# xcore_A.net
KiCad netlist of a schematic drawn in EAGLE
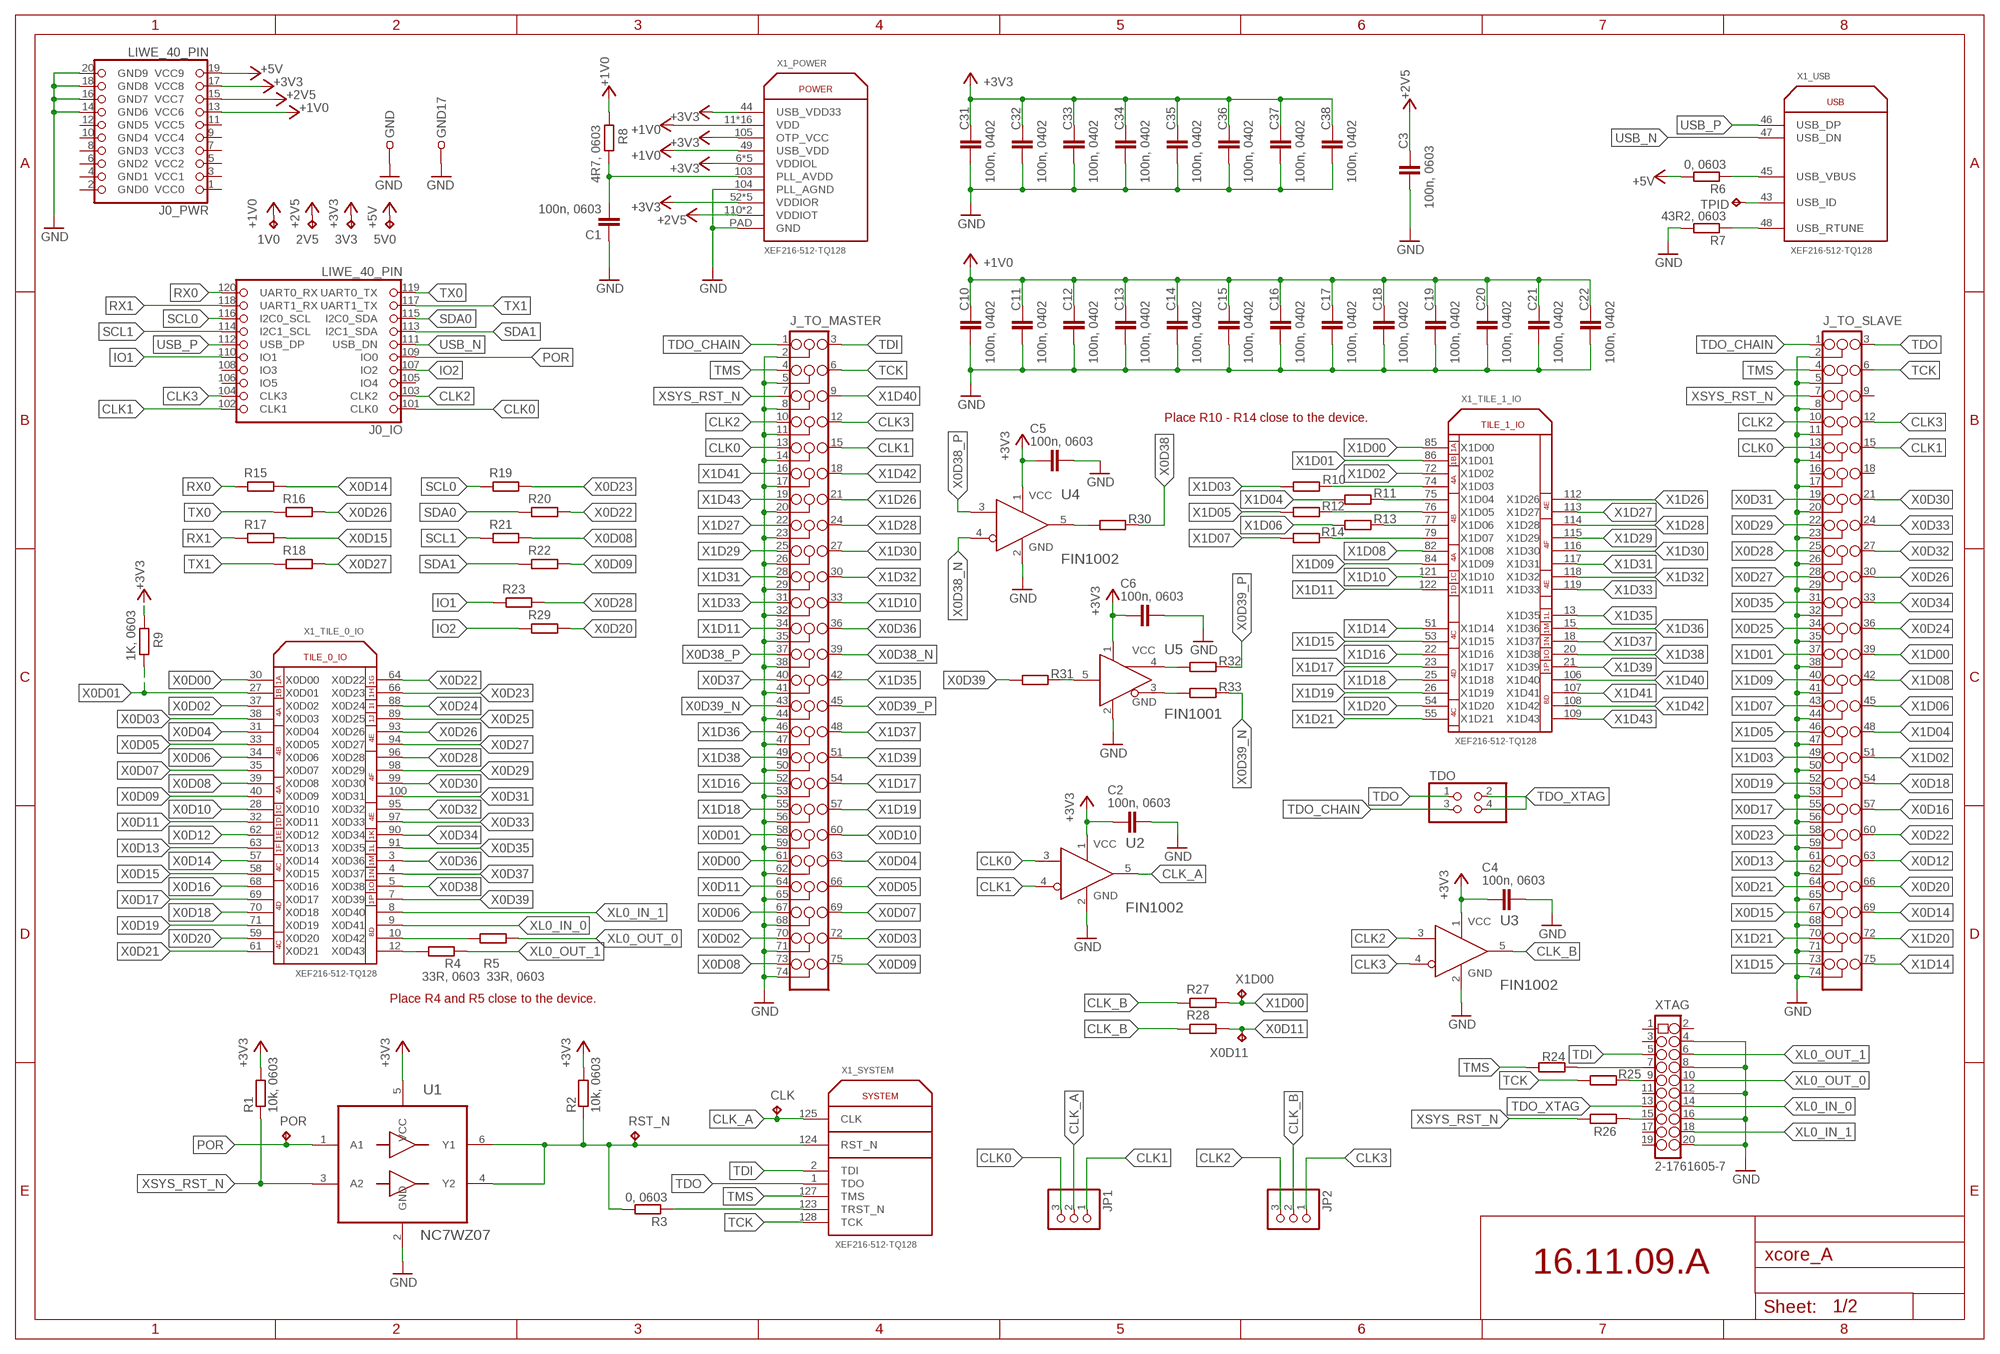
[diagram p0: schematic, sheet 1]
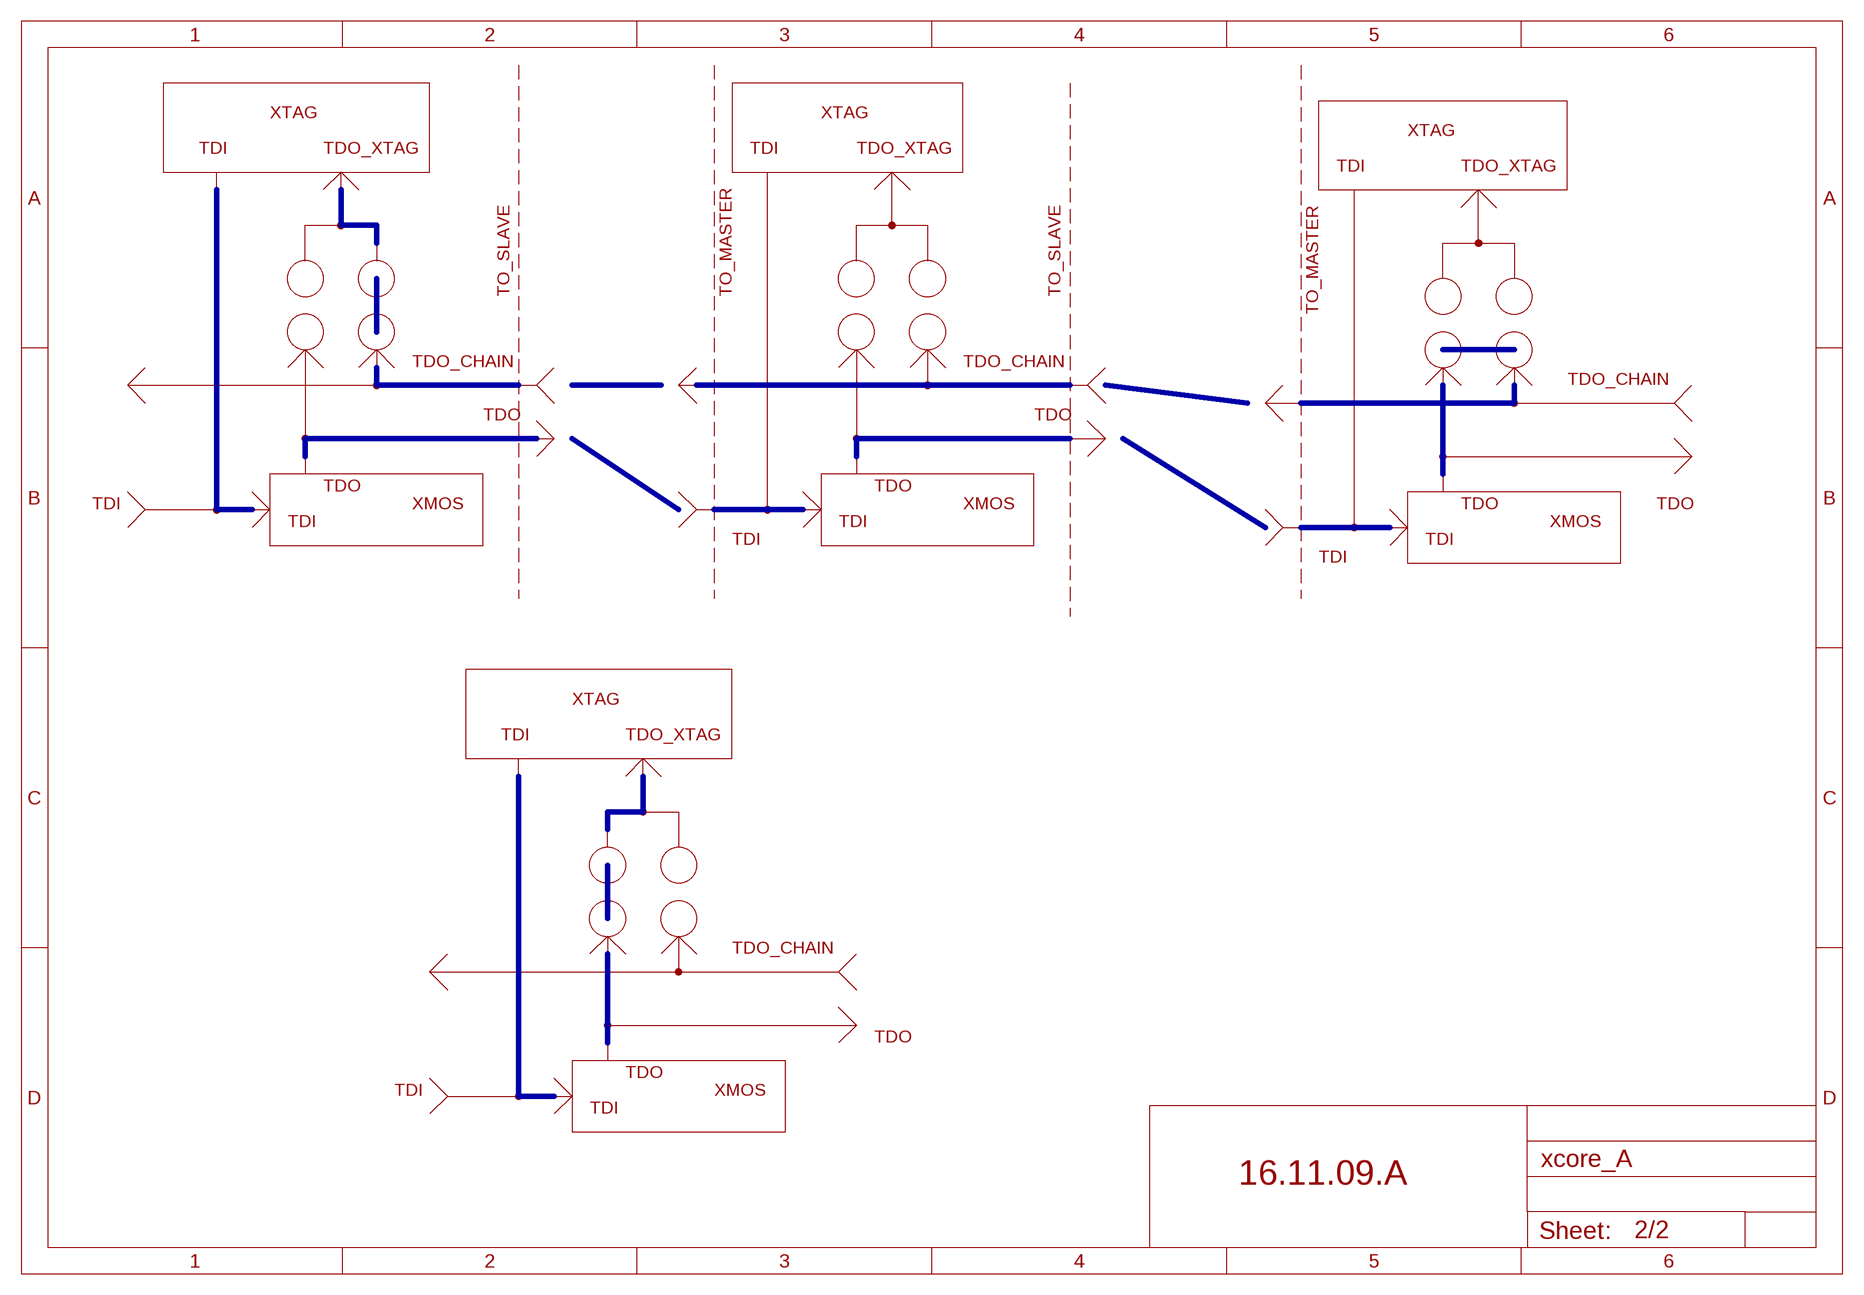
[diagram p1: schematic, sheet 2]

(export (version "E")
  (design (tool "Eeschema 10.0.6"))
  (components
    (comp (ref "1V0")
      (value "TPTP14R")
      (footprint "eagle-import:TP14R")
      (libsource (lib "eagle-import") (part "TPTP14R"))
    )
    (comp (ref "2V5")
      (value "TPTP14R")
      (footprint "eagle-import:TP14R")
      (libsource (lib "eagle-import") (part "TPTP14R"))
    )
    (comp (ref "3V3")
      (value "TPTP14R")
      (footprint "eagle-import:TP14R")
      (libsource (lib "eagle-import") (part "TPTP14R"))
    )
    (comp (ref "5V0")
      (value "TPTP14R")
      (footprint "eagle-import:TP14R")
      (libsource (lib "eagle-import") (part "TPTP14R"))
    )
    (comp (ref "C1")
      (value "100n, 0603")
      (footprint "eagle-import:C0603")
      (libsource (lib "eagle-import") (part "C-EUC0603"))
    )
    (comp (ref "C2")
      (value "100n, 0603")
      (footprint "eagle-import:C0603")
      (libsource (lib "eagle-import") (part "C-EUC0603"))
    )
    (comp (ref "C3")
      (value "100n, 0603")
      (footprint "eagle-import:C0402K")
      (libsource (lib "eagle-import") (part "C-EUC0402K"))
    )
    (comp (ref "C4")
      (value "100n, 0603")
      (footprint "eagle-import:C0603")
      (libsource (lib "eagle-import") (part "C-EUC0603"))
    )
    (comp (ref "C5")
      (value "100n, 0603")
      (footprint "eagle-import:C0603")
      (libsource (lib "eagle-import") (part "C-EUC0603"))
    )
    (comp (ref "C6")
      (value "100n, 0603")
      (footprint "eagle-import:C0603")
      (libsource (lib "eagle-import") (part "C-EUC0603"))
    )
    (comp (ref "C10")
      (value "100n, 0402")
      (footprint "eagle-import:C0402K")
      (libsource (lib "eagle-import") (part "C-EUC0402K"))
    )
    (comp (ref "C11")
      (value "100n, 0402")
      (footprint "eagle-import:C0402K")
      (libsource (lib "eagle-import") (part "C-EUC0402K"))
    )
    (comp (ref "C12")
      (value "100n, 0402")
      (footprint "eagle-import:C0402K")
      (libsource (lib "eagle-import") (part "C-EUC0402K"))
    )
    (comp (ref "C13")
      (value "100n, 0402")
      (footprint "eagle-import:C0402K")
      (libsource (lib "eagle-import") (part "C-EUC0402K"))
    )
    (comp (ref "C14")
      (value "100n, 0402")
      (footprint "eagle-import:C0402K")
      (libsource (lib "eagle-import") (part "C-EUC0402K"))
    )
    (comp (ref "C15")
      (value "100n, 0402")
      (footprint "eagle-import:C0402K")
      (libsource (lib "eagle-import") (part "C-EUC0402K"))
    )
    (comp (ref "C16")
      (value "100n, 0402")
      (footprint "eagle-import:C0402K")
      (libsource (lib "eagle-import") (part "C-EUC0402K"))
    )
    (comp (ref "C17")
      (value "100n, 0402")
      (footprint "eagle-import:C0402K")
      (libsource (lib "eagle-import") (part "C-EUC0402K"))
    )
    (comp (ref "C18")
      (value "100n, 0402")
      (footprint "eagle-import:C0402K")
      (libsource (lib "eagle-import") (part "C-EUC0402K"))
    )
    (comp (ref "C19")
      (value "100n, 0402")
      (footprint "eagle-import:C0402K")
      (libsource (lib "eagle-import") (part "C-EUC0402K"))
    )
    (comp (ref "C20")
      (value "100n, 0402")
      (footprint "eagle-import:C0402K")
      (libsource (lib "eagle-import") (part "C-EUC0402K"))
    )
    (comp (ref "C21")
      (value "100n, 0402")
      (footprint "eagle-import:C0402K")
      (libsource (lib "eagle-import") (part "C-EUC0402K"))
    )
    (comp (ref "C22")
      (value "100n, 0402")
      (footprint "eagle-import:C0402K")
      (libsource (lib "eagle-import") (part "C-EUC0402K"))
    )
    (comp (ref "C31")
      (value "100n, 0402")
      (footprint "eagle-import:C0402K")
      (libsource (lib "eagle-import") (part "C-EUC0402K"))
    )
    (comp (ref "C32")
      (value "100n, 0402")
      (footprint "eagle-import:C0402K")
      (libsource (lib "eagle-import") (part "C-EUC0402K"))
    )
    (comp (ref "C33")
      (value "100n, 0402")
      (footprint "eagle-import:C0402K")
      (libsource (lib "eagle-import") (part "C-EUC0402K"))
    )
    (comp (ref "C34")
      (value "100n, 0402")
      (footprint "eagle-import:C0402K")
      (libsource (lib "eagle-import") (part "C-EUC0402K"))
    )
    (comp (ref "C35")
      (value "100n, 0402")
      (footprint "eagle-import:C0402K")
      (libsource (lib "eagle-import") (part "C-EUC0402K"))
    )
    (comp (ref "C36")
      (value "100n, 0402")
      (footprint "eagle-import:C0402K")
      (libsource (lib "eagle-import") (part "C-EUC0402K"))
    )
    (comp (ref "C37")
      (value "100n, 0402")
      (footprint "eagle-import:C0402K")
      (libsource (lib "eagle-import") (part "C-EUC0402K"))
    )
    (comp (ref "C38")
      (value "100n, 0402")
      (footprint "eagle-import:C0402K")
      (libsource (lib "eagle-import") (part "C-EUC0402K"))
    )
    (comp (ref "CLK")
      (value "TPTP14R")
      (footprint "eagle-import:TP14R")
      (libsource (lib "eagle-import") (part "TPTP14R"))
    )
    (comp (ref "GND")
      (value "TEST-22-MULTICOMP")
      (footprint "eagle-import:TEST_1MM")
      (libsource (lib "eagle-import") (part "TEST-22-MULTICOMP"))
    )
    (comp (ref "GND17")
      (value "TEST-22-MULTICOMP")
      (footprint "eagle-import:TEST_1MM")
      (libsource (lib "eagle-import") (part "TEST-22-MULTICOMP"))
    )
    (comp (ref "J0")
      (value "LIWE_40_PIN")
      (footprint "eagle-import:LIWE_40_PIN_8X8")
      (libsource (lib "eagle-import") (part "LIWE_40_PIN"))
    )
    (comp (ref "JP1")
      (value "PINHD-1X3")
      (footprint "eagle-import:1X03")
      (libsource (lib "eagle-import") (part "PINHD-1X3"))
    )
    (comp (ref "JP2")
      (value "PINHD-1X3")
      (footprint "eagle-import:1X03")
      (libsource (lib "eagle-import") (part "PINHD-1X3"))
    )
    (comp (ref "J_TO_MASTER")
      (value "TSW-125-08-G-T-RA")
      (footprint "eagle-import:3X25_90_M")
      (libsource (lib "eagle-import") (part "PINHD-3X25/90/M"))
    )
    (comp (ref "J_TO_SLAVE")
      (value "TSW-125-08-G-T-RA")
      (footprint "eagle-import:3X25_90")
      (libsource (lib "eagle-import") (part "PINHD-3X25/90"))
    )
    (comp (ref "POR")
      (value "TPTP14R")
      (footprint "eagle-import:TP14R")
      (libsource (lib "eagle-import") (part "TPTP14R"))
    )
    (comp (ref "R1")
      (value "10k, 0603")
      (footprint "eagle-import:R0603")
      (libsource (lib "eagle-import") (part "R-EU_R0603"))
    )
    (comp (ref "R2")
      (value "10k, 0603")
      (footprint "eagle-import:R0603")
      (libsource (lib "eagle-import") (part "R-EU_R0603"))
    )
    (comp (ref "R3")
      (value "0, 0603")
      (footprint "eagle-import:R0603")
      (libsource (lib "eagle-import") (part "R-EU_R0603"))
    )
    (comp (ref "R4")
      (value "33R, 0603")
      (footprint "eagle-import:R0603")
      (libsource (lib "eagle-import") (part "R-EU_R0603"))
    )
    (comp (ref "R5")
      (value "33R, 0603")
      (footprint "eagle-import:R0603")
      (libsource (lib "eagle-import") (part "R-EU_R0603"))
    )
    (comp (ref "R6")
      (value "0, 0603")
      (footprint "eagle-import:R0603")
      (libsource (lib "eagle-import") (part "R-EU_R0603"))
    )
    (comp (ref "R7")
      (value "43R2, 0603")
      (footprint "eagle-import:R0603")
      (libsource (lib "eagle-import") (part "R-EU_R0603"))
    )
    (comp (ref "R8")
      (value "4R7, 0603")
      (footprint "eagle-import:R0603")
      (libsource (lib "eagle-import") (part "R-EU_R0603"))
    )
    (comp (ref "R9")
      (value "1K, 0603")
      (footprint "eagle-import:R0603")
      (libsource (lib "eagle-import") (part "R-EU_R0603"))
    )
    (comp (ref "R10")
      (value "R-EU_R0603")
      (footprint "eagle-import:R0603")
      (libsource (lib "eagle-import") (part "R-EU_R0603"))
    )
    (comp (ref "R11")
      (value "R-EU_R0603")
      (footprint "eagle-import:R0603")
      (libsource (lib "eagle-import") (part "R-EU_R0603"))
    )
    (comp (ref "R12")
      (value "R-EU_R0603")
      (footprint "eagle-import:R0603")
      (libsource (lib "eagle-import") (part "R-EU_R0603"))
    )
    (comp (ref "R13")
      (value "R-EU_R0603")
      (footprint "eagle-import:R0603")
      (libsource (lib "eagle-import") (part "R-EU_R0603"))
    )
    (comp (ref "R14")
      (value "R-EU_R0603")
      (footprint "eagle-import:R0603")
      (libsource (lib "eagle-import") (part "R-EU_R0603"))
    )
    (comp (ref "R15")
      (value "R-EU_R0603")
      (footprint "eagle-import:R0603")
      (libsource (lib "eagle-import") (part "R-EU_R0603"))
    )
    (comp (ref "R16")
      (value "R-EU_R0603")
      (footprint "eagle-import:R0603")
      (libsource (lib "eagle-import") (part "R-EU_R0603"))
    )
    (comp (ref "R17")
      (value "R-EU_R0603")
      (footprint "eagle-import:R0603")
      (libsource (lib "eagle-import") (part "R-EU_R0603"))
    )
    (comp (ref "R18")
      (value "R-EU_R0603")
      (footprint "eagle-import:R0603")
      (libsource (lib "eagle-import") (part "R-EU_R0603"))
    )
    (comp (ref "R19")
      (value "R-EU_R0603")
      (footprint "eagle-import:R0603")
      (libsource (lib "eagle-import") (part "R-EU_R0603"))
    )
    (comp (ref "R20")
      (value "R-EU_R0603")
      (footprint "eagle-import:R0603")
      (libsource (lib "eagle-import") (part "R-EU_R0603"))
    )
    (comp (ref "R21")
      (value "R-EU_R0603")
      (footprint "eagle-import:R0603")
      (libsource (lib "eagle-import") (part "R-EU_R0603"))
    )
    (comp (ref "R22")
      (value "R-EU_R0603")
      (footprint "eagle-import:R0603")
      (libsource (lib "eagle-import") (part "R-EU_R0603"))
    )
    (comp (ref "R23")
      (value "R-EU_R0603")
      (footprint "eagle-import:R0603")
      (libsource (lib "eagle-import") (part "R-EU_R0603"))
    )
    (comp (ref "R24")
      (value "R-EU_R0603")
      (footprint "eagle-import:R0603")
      (libsource (lib "eagle-import") (part "R-EU_R0603"))
    )
    (comp (ref "R25")
      (value "R-EU_R0603")
      (footprint "eagle-import:R0603")
      (libsource (lib "eagle-import") (part "R-EU_R0603"))
    )
    (comp (ref "R26")
      (value "R-EU_R0603")
      (footprint "eagle-import:R0603")
      (libsource (lib "eagle-import") (part "R-EU_R0603"))
    )
    (comp (ref "R27")
      (value "R-EU_R0603")
      (footprint "eagle-import:R0603")
      (libsource (lib "eagle-import") (part "R-EU_R0603"))
    )
    (comp (ref "R28")
      (value "R-EU_R0603")
      (footprint "eagle-import:R0603")
      (libsource (lib "eagle-import") (part "R-EU_R0603"))
    )
    (comp (ref "R29")
      (value "R-EU_R0603")
      (footprint "eagle-import:R0603")
      (libsource (lib "eagle-import") (part "R-EU_R0603"))
    )
    (comp (ref "R30")
      (value "R-EU_R0603")
      (footprint "eagle-import:R0603")
      (libsource (lib "eagle-import") (part "R-EU_R0603"))
    )
    (comp (ref "R31")
      (value "R-EU_R0603")
      (footprint "eagle-import:R0603")
      (libsource (lib "eagle-import") (part "R-EU_R0603"))
    )
    (comp (ref "R32")
      (value "R-EU_R0603")
      (footprint "eagle-import:R0603")
      (libsource (lib "eagle-import") (part "R-EU_R0603"))
    )
    (comp (ref "R33")
      (value "R-EU_R0603")
      (footprint "eagle-import:R0603")
      (libsource (lib "eagle-import") (part "R-EU_R0603"))
    )
    (comp (ref "RST_N")
      (value "TPTP14R")
      (footprint "eagle-import:TP14R")
      (libsource (lib "eagle-import") (part "TPTP14R"))
    )
    (comp (ref "TDO")
      (value "PINHD-2X2")
      (footprint "eagle-import:2X02")
      (libsource (lib "eagle-import") (part "PINHD-2X2"))
    )
    (comp (ref "TPID")
      (value "TPB1,27")
      (footprint "eagle-import:B1,27")
      (libsource (lib "eagle-import") (part "TPB1,27"))
    )
    (comp (ref "U1")
      (value "NC7WZ07")
      (footprint "eagle-import:SOT65P210X110-6N")
      (libsource (lib "eagle-import") (part "NC7WZ07"))
    )
    (comp (ref "U2")
      (value "FIN1002")
      (footprint "eagle-import:SOT95P280X140-5N")
      (libsource (lib "eagle-import") (part "FIN1002"))
    )
    (comp (ref "U3")
      (value "FIN1002")
      (footprint "eagle-import:SOT95P280X140-5N")
      (libsource (lib "eagle-import") (part "FIN1002"))
    )
    (comp (ref "U4")
      (value "FIN1002")
      (footprint "eagle-import:SOT95P280X140-5N")
      (libsource (lib "eagle-import") (part "FIN1002"))
    )
    (comp (ref "U5")
      (value "FIN1001")
      (footprint "eagle-import:SOT95P280X140-5N")
      (libsource (lib "eagle-import") (part "FIN1001"))
    )
    (comp (ref "X0D11")
      (value "TPTP14R")
      (footprint "eagle-import:TP14R")
      (libsource (lib "eagle-import") (part "TPTP14R"))
    )
    (comp (ref "X1")
      (value "XEF216-512-TQ128")
      (footprint "eagle-import:TQFP128")
      (libsource (lib "eagle-import") (part "XEF216-512-TQ128"))
    )
    (comp (ref "X1D00")
      (value "TPTP14R")
      (footprint "eagle-import:TP14R")
      (libsource (lib "eagle-import") (part "TPTP14R"))
    )
    (comp (ref "XTAG")
      (value "2-1761605-7")
      (footprint "eagle-import:2X10")
      (libsource (lib "eagle-import") (part "PINHD-2X10"))
    )
  )
  (nets
    (net (code "1") (name "+1V0") (class "Default")
      (node (ref "1V0") (pin "TP") (pinfunction "TP_TP") (pintype "input"))
      (node (ref "C10") (pin "2") (pinfunction "2_2") (pintype "passive"))
      (node (ref "C11") (pin "2") (pinfunction "2_2") (pintype "passive"))
      (node (ref "C12") (pin "2") (pinfunction "2_2") (pintype "passive"))
      (node (ref "C13") (pin "2") (pinfunction "2_2") (pintype "passive"))
      (node (ref "C14") (pin "2") (pinfunction "2_2") (pintype "passive"))
      (node (ref "C15") (pin "2") (pinfunction "2_2") (pintype "passive"))
      (node (ref "C16") (pin "2") (pinfunction "2_2") (pintype "passive"))
      (node (ref "C17") (pin "2") (pinfunction "2_2") (pintype "passive"))
      (node (ref "C18") (pin "2") (pinfunction "2_2") (pintype "passive"))
      (node (ref "C19") (pin "2") (pinfunction "2_2") (pintype "passive"))
      (node (ref "C20") (pin "2") (pinfunction "2_2") (pintype "passive"))
      (node (ref "C21") (pin "2") (pinfunction "2_2") (pintype "passive"))
      (node (ref "C22") (pin "2") (pinfunction "2_2") (pintype "passive"))
      (node (ref "J0") (pin "13") (pinfunction "VCC6_13") (pintype "passive"))
      (node (ref "R8") (pin "1") (pinfunction "1_1") (pintype "passive"))
      (node (ref "X1") (pin "101") (pinfunction "VDD_101") (pintype "bidirectional"))
      (node (ref "X1") (pin "102") (pinfunction "VDD_102") (pintype "bidirectional"))
      (node (ref "X1") (pin "11") (pinfunction "VDD_11") (pintype "bidirectional"))
      (node (ref "X1") (pin "120") (pinfunction "VDD_120") (pintype "bidirectional"))
      (node (ref "X1") (pin "126") (pinfunction "VDD_126") (pintype "bidirectional"))
      (node (ref "X1") (pin "16") (pinfunction "VDD_16") (pintype "bidirectional"))
      (node (ref "X1") (pin "17") (pinfunction "VDD_17") (pintype "bidirectional"))
      (node (ref "X1") (pin "24") (pinfunction "VDD_24") (pintype "bidirectional"))
      (node (ref "X1") (pin "36") (pinfunction "VDD_36") (pintype "bidirectional"))
      (node (ref "X1") (pin "41") (pinfunction "VDD_41") (pintype "bidirectional"))
      (node (ref "X1") (pin "49") (pinfunction "USB_VDD_49") (pintype "bidirectional"))
      (node (ref "X1") (pin "56") (pinfunction "VDD_56") (pintype "bidirectional"))
      (node (ref "X1") (pin "60") (pinfunction "VDD_60") (pintype "bidirectional"))
      (node (ref "X1") (pin "73") (pinfunction "VDD_73") (pintype "bidirectional"))
      (node (ref "X1") (pin "80") (pinfunction "VDD_80") (pintype "bidirectional"))
      (node (ref "X1") (pin "81") (pinfunction "VDD_81") (pintype "bidirectional"))
      (node (ref "X1") (pin "87") (pinfunction "VDD_87") (pintype "bidirectional"))
    )
    (net (code "2") (name "+2V5") (class "Default")
      (node (ref "2V5") (pin "TP") (pinfunction "TP_TP") (pintype "input"))
      (node (ref "C3") (pin "2") (pinfunction "2_2") (pintype "passive"))
      (node (ref "J0") (pin "15") (pinfunction "VCC7_15") (pintype "passive"))
      (node (ref "X1") (pin "110") (pinfunction "VDDIOT_110") (pintype "bidirectional"))
      (node (ref "X1") (pin "111") (pinfunction "VDDIOT_111") (pintype "bidirectional"))
    )
    (net (code "3") (name "+3V3") (class "Default")
      (node (ref "3V3") (pin "TP") (pinfunction "TP_TP") (pintype "input"))
      (node (ref "C2") (pin "2") (pinfunction "2_2") (pintype "passive"))
      (node (ref "C31") (pin "2") (pinfunction "2_2") (pintype "passive"))
      (node (ref "C32") (pin "2") (pinfunction "2_2") (pintype "passive"))
      (node (ref "C33") (pin "2") (pinfunction "2_2") (pintype "passive"))
      (node (ref "C34") (pin "2") (pinfunction "2_2") (pintype "passive"))
      (node (ref "C35") (pin "2") (pinfunction "2_2") (pintype "passive"))
      (node (ref "C36") (pin "2") (pinfunction "2_2") (pintype "passive"))
      (node (ref "C37") (pin "2") (pinfunction "2_2") (pintype "passive"))
      (node (ref "C38") (pin "2") (pinfunction "2_2") (pintype "passive"))
      (node (ref "C4") (pin "2") (pinfunction "2_2") (pintype "passive"))
      (node (ref "C5") (pin "2") (pinfunction "2_2") (pintype "passive"))
      (node (ref "C6") (pin "2") (pinfunction "2_2") (pintype "passive"))
      (node (ref "J0") (pin "17") (pinfunction "VCC8_17") (pintype "passive"))
      (node (ref "R1") (pin "2") (pinfunction "2_2") (pintype "passive"))
      (node (ref "R2") (pin "2") (pinfunction "2_2") (pintype "passive"))
      (node (ref "R9") (pin "1") (pinfunction "1_1") (pintype "passive"))
      (node (ref "U1") (pin "5") (pinfunction "VCC_5") (pintype "power_in"))
      (node (ref "U2") (pin "1") (pinfunction "VCC_1") (pintype "power_in"))
      (node (ref "U3") (pin "1") (pinfunction "VCC_1") (pintype "power_in"))
      (node (ref "U4") (pin "1") (pinfunction "VCC_1") (pintype "power_in"))
      (node (ref "U5") (pin "1") (pinfunction "VCC_1") (pintype "power_in"))
      (node (ref "X1") (pin "105") (pinfunction "OTP_VCC_105") (pintype "bidirectional"))
      (node (ref "X1") (pin "14") (pinfunction "VDDIOL_14") (pintype "bidirectional"))
      (node (ref "X1") (pin "19") (pinfunction "VDDIOL_19") (pintype "bidirectional"))
      (node (ref "X1") (pin "29") (pinfunction "VDDIOL_29") (pintype "bidirectional"))
      (node (ref "X1") (pin "42") (pinfunction "VDDIOL_42") (pintype "bidirectional"))
      (node (ref "X1") (pin "44") (pinfunction "USB_VDD33_44") (pintype "bidirectional"))
      (node (ref "X1") (pin "52") (pinfunction "VDDIOR_52") (pintype "bidirectional"))
      (node (ref "X1") (pin "6") (pinfunction "VDDIOL_6") (pintype "bidirectional"))
      (node (ref "X1") (pin "67") (pinfunction "VDDIOR_67") (pintype "bidirectional"))
      (node (ref "X1") (pin "78") (pinfunction "VDDIOR_78") (pintype "bidirectional"))
      (node (ref "X1") (pin "83") (pinfunction "VDDIOR_83") (pintype "bidirectional"))
      (node (ref "X1") (pin "92") (pinfunction "VDDIOR_92") (pintype "bidirectional"))
    )
    (net (code "4") (name "+5V") (class "Default")
      (node (ref "5V0") (pin "TP") (pinfunction "TP_TP") (pintype "input"))
      (node (ref "J0") (pin "19") (pinfunction "VCC9_19") (pintype "passive"))
      (node (ref "R6") (pin "2") (pinfunction "2_2") (pintype "passive"))
    )
    (net (code "5") (name "CLK0") (class "Default")
      (node (ref "J0") (pin "101") (pinfunction "CLK0_101") (pintype "passive"))
      (node (ref "JP1") (pin "3") (pinfunction "3_3") (pintype "passive"))
      (node (ref "J_TO_MASTER") (pin "13") (pinfunction "13_13") (pintype "passive"))
      (node (ref "J_TO_SLAVE") (pin "13") (pinfunction "13_13") (pintype "passive"))
      (node (ref "U2") (pin "3") (pinfunction "RIN+_3") (pintype "input"))
    )
    (net (code "6") (name "CLK1") (class "Default")
      (node (ref "J0") (pin "102") (pinfunction "CLK1_102") (pintype "passive"))
      (node (ref "JP1") (pin "1") (pinfunction "1_1") (pintype "passive"))
      (node (ref "J_TO_MASTER") (pin "15") (pinfunction "15_15") (pintype "passive"))
      (node (ref "J_TO_SLAVE") (pin "15") (pinfunction "15_15") (pintype "passive"))
      (node (ref "U2") (pin "4") (pinfunction "RIN-_4") (pintype "input"))
    )
    (net (code "7") (name "CLK2") (class "Default")
      (node (ref "J0") (pin "103") (pinfunction "CLK2_103") (pintype "passive"))
      (node (ref "JP2") (pin "3") (pinfunction "3_3") (pintype "passive"))
      (node (ref "J_TO_MASTER") (pin "10") (pinfunction "10_10") (pintype "passive"))
      (node (ref "J_TO_SLAVE") (pin "10") (pinfunction "10_10") (pintype "passive"))
      (node (ref "U3") (pin "3") (pinfunction "RIN+_3") (pintype "input"))
    )
    (net (code "8") (name "CLK3") (class "Default")
      (node (ref "J0") (pin "104") (pinfunction "CLK3_104") (pintype "passive"))
      (node (ref "JP2") (pin "1") (pinfunction "1_1") (pintype "passive"))
      (node (ref "J_TO_MASTER") (pin "12") (pinfunction "12_12") (pintype "passive"))
      (node (ref "J_TO_SLAVE") (pin "12") (pinfunction "12_12") (pintype "passive"))
      (node (ref "U3") (pin "4") (pinfunction "RIN-_4") (pintype "input"))
    )
    (net (code "9") (name "CLK_A") (class "Default")
      (node (ref "CLK") (pin "TP") (pinfunction "TP_TP") (pintype "input"))
      (node (ref "JP1") (pin "2") (pinfunction "2_2") (pintype "passive"))
      (node (ref "U2") (pin "5") (pinfunction "ROUT_5") (pintype "output"))
      (node (ref "X1") (pin "125") (pinfunction "CLK_125") (pintype "bidirectional"))
    )
    (net (code "10") (name "CLK_B") (class "Default")
      (node (ref "JP2") (pin "2") (pinfunction "2_2") (pintype "passive"))
      (node (ref "R27") (pin "1") (pinfunction "1_1") (pintype "passive"))
      (node (ref "R28") (pin "1") (pinfunction "1_1") (pintype "passive"))
      (node (ref "U3") (pin "5") (pinfunction "ROUT_5") (pintype "output"))
    )
    (net (code "11") (name "GND") (class "Default")
      (node (ref "C1") (pin "1") (pinfunction "1_1") (pintype "passive"))
      (node (ref "C10") (pin "1") (pinfunction "1_1") (pintype "passive"))
      (node (ref "C11") (pin "1") (pinfunction "1_1") (pintype "passive"))
      (node (ref "C12") (pin "1") (pinfunction "1_1") (pintype "passive"))
      (node (ref "C13") (pin "1") (pinfunction "1_1") (pintype "passive"))
      (node (ref "C14") (pin "1") (pinfunction "1_1") (pintype "passive"))
      (node (ref "C15") (pin "1") (pinfunction "1_1") (pintype "passive"))
      (node (ref "C16") (pin "1") (pinfunction "1_1") (pintype "passive"))
      (node (ref "C17") (pin "1") (pinfunction "1_1") (pintype "passive"))
      (node (ref "C18") (pin "1") (pinfunction "1_1") (pintype "passive"))
      (node (ref "C19") (pin "1") (pinfunction "1_1") (pintype "passive"))
      (node (ref "C2") (pin "1") (pinfunction "1_1") (pintype "passive"))
      (node (ref "C20") (pin "1") (pinfunction "1_1") (pintype "passive"))
      (node (ref "C21") (pin "1") (pinfunction "1_1") (pintype "passive"))
      (node (ref "C22") (pin "1") (pinfunction "1_1") (pintype "passive"))
      (node (ref "C3") (pin "1") (pinfunction "1_1") (pintype "passive"))
      (node (ref "C31") (pin "1") (pinfunction "1_1") (pintype "passive"))
      (node (ref "C32") (pin "1") (pinfunction "1_1") (pintype "passive"))
      (node (ref "C33") (pin "1") (pinfunction "1_1") (pintype "passive"))
      (node (ref "C34") (pin "1") (pinfunction "1_1") (pintype "passive"))
      (node (ref "C35") (pin "1") (pinfunction "1_1") (pintype "passive"))
      (node (ref "C36") (pin "1") (pinfunction "1_1") (pintype "passive"))
      (node (ref "C37") (pin "1") (pinfunction "1_1") (pintype "passive"))
      (node (ref "C38") (pin "1") (pinfunction "1_1") (pintype "passive"))
      (node (ref "C4") (pin "1") (pinfunction "1_1") (pintype "passive"))
      (node (ref "C5") (pin "1") (pinfunction "1_1") (pintype "passive"))
      (node (ref "C6") (pin "1") (pinfunction "1_1") (pintype "passive"))
      (node (ref "GND") (pin "1") (pinfunction "1_1") (pintype "passive"))
      (node (ref "GND17") (pin "1") (pinfunction "1_1") (pintype "passive"))
      (node (ref "J0") (pin "14") (pinfunction "GND6_14") (pintype "passive"))
      (node (ref "J0") (pin "16") (pinfunction "GND7_16") (pintype "passive"))
      (node (ref "J0") (pin "18") (pinfunction "GND8_18") (pintype "passive"))
      (node (ref "J0") (pin "20") (pinfunction "GND9_20") (pintype "passive"))
      (node (ref "J_TO_MASTER") (pin "11") (pinfunction "11_11") (pintype "passive"))
      (node (ref "J_TO_MASTER") (pin "14") (pinfunction "14_14") (pintype "passive"))
      (node (ref "J_TO_MASTER") (pin "17") (pinfunction "17_17") (pintype "passive"))
      (node (ref "J_TO_MASTER") (pin "2") (pinfunction "2_2") (pintype "passive"))
      (node (ref "J_TO_MASTER") (pin "20") (pinfunction "20_20") (pintype "passive"))
      (node (ref "J_TO_MASTER") (pin "23") (pinfunction "23_23") (pintype "passive"))
      (node (ref "J_TO_MASTER") (pin "26") (pinfunction "26_26") (pintype "passive"))
      (node (ref "J_TO_MASTER") (pin "29") (pinfunction "29_29") (pintype "passive"))
      (node (ref "J_TO_MASTER") (pin "32") (pinfunction "32_32") (pintype "passive"))
      (node (ref "J_TO_MASTER") (pin "35") (pinfunction "35_35") (pintype "passive"))
      (node (ref "J_TO_MASTER") (pin "38") (pinfunction "38_38") (pintype "passive"))
      (node (ref "J_TO_MASTER") (pin "41") (pinfunction "41_41") (pintype "passive"))
      (node (ref "J_TO_MASTER") (pin "44") (pinfunction "44_44") (pintype "passive"))
      (node (ref "J_TO_MASTER") (pin "47") (pinfunction "47_47") (pintype "passive"))
      (node (ref "J_TO_MASTER") (pin "5") (pinfunction "5_5") (pintype "passive"))
      (node (ref "J_TO_MASTER") (pin "50") (pinfunction "50_50") (pintype "passive"))
      (node (ref "J_TO_MASTER") (pin "53") (pinfunction "53_53") (pintype "passive"))
      (node (ref "J_TO_MASTER") (pin "56") (pinfunction "56_56") (pintype "passive"))
      (node (ref "J_TO_MASTER") (pin "59") (pinfunction "59_59") (pintype "passive"))
      (node (ref "J_TO_MASTER") (pin "62") (pinfunction "62_62") (pintype "passive"))
      (node (ref "J_TO_MASTER") (pin "65") (pinfunction "65_65") (pintype "passive"))
      (node (ref "J_TO_MASTER") (pin "68") (pinfunction "68_68") (pintype "passive"))
      (node (ref "J_TO_MASTER") (pin "71") (pinfunction "71_71") (pintype "passive"))
      (node (ref "J_TO_MASTER") (pin "74") (pinfunction "74_74") (pintype "passive"))
      (node (ref "J_TO_MASTER") (pin "8") (pinfunction "8_8") (pintype "passive"))
      (node (ref "J_TO_SLAVE") (pin "11") (pinfunction "11_11") (pintype "passive"))
      (node (ref "J_TO_SLAVE") (pin "14") (pinfunction "14_14") (pintype "passive"))
      (node (ref "J_TO_SLAVE") (pin "17") (pinfunction "17_17") (pintype "passive"))
      (node (ref "J_TO_SLAVE") (pin "2") (pinfunction "2_2") (pintype "passive"))
      (node (ref "J_TO_SLAVE") (pin "20") (pinfunction "20_20") (pintype "passive"))
      (node (ref "J_TO_SLAVE") (pin "23") (pinfunction "23_23") (pintype "passive"))
      (node (ref "J_TO_SLAVE") (pin "26") (pinfunction "26_26") (pintype "passive"))
      (node (ref "J_TO_SLAVE") (pin "29") (pinfunction "29_29") (pintype "passive"))
      (node (ref "J_TO_SLAVE") (pin "32") (pinfunction "32_32") (pintype "passive"))
      (node (ref "J_TO_SLAVE") (pin "35") (pinfunction "35_35") (pintype "passive"))
      (node (ref "J_TO_SLAVE") (pin "38") (pinfunction "38_38") (pintype "passive"))
      (node (ref "J_TO_SLAVE") (pin "41") (pinfunction "41_41") (pintype "passive"))
      (node (ref "J_TO_SLAVE") (pin "44") (pinfunction "44_44") (pintype "passive"))
      (node (ref "J_TO_SLAVE") (pin "47") (pinfunction "47_47") (pintype "passive"))
      (node (ref "J_TO_SLAVE") (pin "5") (pinfunction "5_5") (pintype "passive"))
      (node (ref "J_TO_SLAVE") (pin "50") (pinfunction "50_50") (pintype "passive"))
      (node (ref "J_TO_SLAVE") (pin "53") (pinfunction "53_53") (pintype "passive"))
      (node (ref "J_TO_SLAVE") (pin "56") (pinfunction "56_56") (pintype "passive"))
      (node (ref "J_TO_SLAVE") (pin "59") (pinfunction "59_59") (pintype "passive"))
      (node (ref "J_TO_SLAVE") (pin "62") (pinfunction "62_62") (pintype "passive"))
      (node (ref "J_TO_SLAVE") (pin "65") (pinfunction "65_65") (pintype "passive"))
      (node (ref "J_TO_SLAVE") (pin "68") (pinfunction "68_68") (pintype "passive"))
      (node (ref "J_TO_SLAVE") (pin "71") (pinfunction "71_71") (pintype "passive"))
      (node (ref "J_TO_SLAVE") (pin "74") (pinfunction "74_74") (pintype "passive"))
      (node (ref "J_TO_SLAVE") (pin "8") (pinfunction "8_8") (pintype "passive"))
      (node (ref "R7") (pin "2") (pinfunction "2_2") (pintype "passive"))
      (node (ref "U1") (pin "2") (pinfunction "GND_2") (pintype "passive"))
      (node (ref "U2") (pin "2") (pinfunction "GND_2") (pintype "passive"))
      (node (ref "U3") (pin "2") (pinfunction "GND_2") (pintype "passive"))
      (node (ref "U4") (pin "2") (pinfunction "GND_2") (pintype "passive"))
      (node (ref "U5") (pin "2") (pinfunction "GND_2") (pintype "passive"))
      (node (ref "X1") (pin "104") (pinfunction "PLL_AGND_104") (pintype "bidirectional"))
      (node (ref "X1") (pin "PAD") (pinfunction "GND_PAD") (pintype "bidirectional"))
      (node (ref "XTAG") (pin "12") (pinfunction "12_12") (pintype "passive"))
      (node (ref "XTAG") (pin "16") (pinfunction "16_16") (pintype "passive"))
      (node (ref "XTAG") (pin "20") (pinfunction "20_20") (pintype "passive"))
      (node (ref "XTAG") (pin "4") (pinfunction "4_4") (pintype "passive"))
      (node (ref "XTAG") (pin "8") (pinfunction "8_8") (pintype "passive"))
    )
    (net (code "12") (name "IO1") (class "Default")
      (node (ref "J0") (pin "110") (pinfunction "IO1_110") (pintype "passive"))
      (node (ref "R23") (pin "1") (pinfunction "1_1") (pintype "passive"))
    )
    (net (code "13") (name "IO2") (class "Default")
      (node (ref "J0") (pin "107") (pinfunction "IO2_107") (pintype "passive"))
      (node (ref "R29") (pin "1") (pinfunction "1_1") (pintype "passive"))
    )
    (net (code "14") (name "Net-(R24-Pad2)") (class "Default")
      (node (ref "R24") (pin "2") (pinfunction "2_2") (pintype "passive"))
      (node (ref "XTAG") (pin "7") (pinfunction "7_7") (pintype "passive"))
    )
    (net (code "15") (name "Net-(R25-Pad2)") (class "Default")
      (node (ref "R25") (pin "2") (pinfunction "2_2") (pintype "passive"))
      (node (ref "XTAG") (pin "9") (pinfunction "9_9") (pintype "passive"))
    )
    (net (code "16") (name "Net-(R26-Pad2)") (class "Default")
      (node (ref "R26") (pin "2") (pinfunction "2_2") (pintype "passive"))
      (node (ref "XTAG") (pin "15") (pinfunction "15_15") (pintype "passive"))
    )
    (net (code "17") (name "Net-(U1-Y1)") (class "Default")
      (node (ref "R2") (pin "1") (pinfunction "1_1") (pintype "passive"))
      (node (ref "R3") (pin "2") (pinfunction "2_2") (pintype "passive"))
      (node (ref "RST_N") (pin "TP") (pinfunction "TP_TP") (pintype "input"))
      (node (ref "U1") (pin "4") (pinfunction "Y2_4") (pintype "output"))
      (node (ref "U1") (pin "6") (pinfunction "Y1_6") (pintype "output"))
      (node (ref "X1") (pin "124") (pinfunction "RST_N_124") (pintype "bidirectional"))
    )
    (net (code "18") (name "Net-(U4-ROUT)") (class "Default")
      (node (ref "R30") (pin "1") (pinfunction "1_1") (pintype "passive"))
      (node (ref "U4") (pin "5") (pinfunction "ROUT_5") (pintype "output"))
    )
    (net (code "19") (name "Net-(U5-RIN)") (class "Default")
      (node (ref "R31") (pin "2") (pinfunction "2_2") (pintype "passive"))
      (node (ref "U5") (pin "5") (pinfunction "RIN_5") (pintype "input"))
    )
    (net (code "20") (name "Net-(U5-ROUT+)") (class "Default")
      (node (ref "R32") (pin "1") (pinfunction "1_1") (pintype "passive"))
      (node (ref "U5") (pin "4") (pinfunction "ROUT+_4") (pintype "output"))
    )
    (net (code "21") (name "Net-(U5-ROUT-)") (class "Default")
      (node (ref "R33") (pin "1") (pinfunction "1_1") (pintype "passive"))
      (node (ref "U5") (pin "3") (pinfunction "ROUT-_3") (pintype "output"))
    )
    (net (code "22") (name "Net-(X1A-PLL_AVDD)") (class "Default")
      (node (ref "C1") (pin "2") (pinfunction "2_2") (pintype "passive"))
      (node (ref "R8") (pin "2") (pinfunction "2_2") (pintype "passive"))
      (node (ref "X1") (pin "103") (pinfunction "PLL_AVDD_103") (pintype "bidirectional"))
    )
    (net (code "23") (name "Net-(X1B-TRST_N)") (class "Default")
      (node (ref "R3") (pin "1") (pinfunction "1_1") (pintype "passive"))
      (node (ref "X1") (pin "123") (pinfunction "TRST_N_123") (pintype "bidirectional"))
    )
    (net (code "24") (name "Net-(X1C-X0D42)") (class "Default")
      (node (ref "R5") (pin "2") (pinfunction "2_2") (pintype "passive"))
      (node (ref "X1") (pin "10") (pinfunction "X0D42_10") (pintype "bidirectional"))
    )
    (net (code "25") (name "Net-(X1C-X0D43)") (class "Default")
      (node (ref "R4") (pin "2") (pinfunction "2_2") (pintype "passive"))
      (node (ref "X1") (pin "12") (pinfunction "X0D43_12") (pintype "bidirectional"))
    )
    (net (code "26") (name "Net-(X1D-X1D03)") (class "Default")
      (node (ref "R10") (pin "2") (pinfunction "2_2") (pintype "passive"))
      (node (ref "X1") (pin "74") (pinfunction "X1D03_74") (pintype "bidirectional"))
    )
    (net (code "27") (name "Net-(X1D-X1D04)") (class "Default")
      (node (ref "R11") (pin "2") (pinfunction "2_2") (pintype "passive"))
      (node (ref "X1") (pin "75") (pinfunction "X1D04_75") (pintype "bidirectional"))
    )
    (net (code "28") (name "Net-(X1D-X1D05)") (class "Default")
      (node (ref "R12") (pin "2") (pinfunction "2_2") (pintype "passive"))
      (node (ref "X1") (pin "76") (pinfunction "X1D05_76") (pintype "bidirectional"))
    )
    (net (code "29") (name "Net-(X1D-X1D06)") (class "Default")
      (node (ref "R13") (pin "2") (pinfunction "2_2") (pintype "passive"))
      (node (ref "X1") (pin "77") (pinfunction "X1D06_77") (pintype "bidirectional"))
    )
    (net (code "30") (name "Net-(X1D-X1D07)") (class "Default")
      (node (ref "R14") (pin "2") (pinfunction "2_2") (pintype "passive"))
      (node (ref "X1") (pin "79") (pinfunction "X1D07_79") (pintype "bidirectional"))
    )
    (net (code "31") (name "Net-(X1E-USB_ID)") (class "Default")
      (node (ref "TPID") (pin "TP") (pinfunction "TP_TP") (pintype "input"))
      (node (ref "X1") (pin "43") (pinfunction "USB_ID_43") (pintype "bidirectional"))
    )
    (net (code "32") (name "Net-(X1E-USB_RTUNE)") (class "Default")
      (node (ref "R7") (pin "1") (pinfunction "1_1") (pintype "passive"))
      (node (ref "X1") (pin "48") (pinfunction "USB_RTUNE_48") (pintype "bidirectional"))
    )
    (net (code "33") (name "Net-(X1E-USB_VBUS)") (class "Default")
      (node (ref "R6") (pin "1") (pinfunction "1_1") (pintype "passive"))
      (node (ref "X1") (pin "45") (pinfunction "USB_VBUS_45") (pintype "bidirectional"))
    )
    (net (code "34") (name "POR") (class "Default")
      (node (ref "J0") (pin "109") (pinfunction "IO0_109") (pintype "passive"))
      (node (ref "POR") (pin "TP") (pinfunction "TP_TP") (pintype "input"))
      (node (ref "U1") (pin "1") (pinfunction "A1_1") (pintype "input"))
    )
    (net (code "35") (name "RX0") (class "Default")
      (node (ref "J0") (pin "120") (pinfunction "UART0_RX_120") (pintype "passive"))
      (node (ref "R15") (pin "1") (pinfunction "1_1") (pintype "passive"))
    )
    (net (code "36") (name "RX1") (class "Default")
      (node (ref "J0") (pin "118") (pinfunction "UART1_RX_118") (pintype "passive"))
      (node (ref "R17") (pin "1") (pinfunction "1_1") (pintype "passive"))
    )
    (net (code "37") (name "SCL0") (class "Default")
      (node (ref "J0") (pin "116") (pinfunction "I2C0_SCL_116") (pintype "passive"))
      (node (ref "R19") (pin "1") (pinfunction "1_1") (pintype "passive"))
    )
    (net (code "38") (name "SCL1") (class "Default")
      (node (ref "J0") (pin "114") (pinfunction "I2C1_SCL_114") (pintype "passive"))
      (node (ref "R21") (pin "1") (pinfunction "1_1") (pintype "passive"))
    )
    (net (code "39") (name "SDA0") (class "Default")
      (node (ref "J0") (pin "115") (pinfunction "I2C0_SDA_115") (pintype "passive"))
      (node (ref "R20") (pin "1") (pinfunction "1_1") (pintype "passive"))
    )
    (net (code "40") (name "SDA1") (class "Default")
      (node (ref "J0") (pin "113") (pinfunction "I2C1_SDA_113") (pintype "passive"))
      (node (ref "R22") (pin "1") (pinfunction "1_1") (pintype "passive"))
    )
    (net (code "41") (name "TCK") (class "Default")
      (node (ref "J_TO_MASTER") (pin "6") (pinfunction "6_6") (pintype "passive"))
      (node (ref "J_TO_SLAVE") (pin "6") (pinfunction "6_6") (pintype "passive"))
      (node (ref "R25") (pin "1") (pinfunction "1_1") (pintype "passive"))
      (node (ref "X1") (pin "128") (pinfunction "TCK_128") (pintype "bidirectional"))
    )
    (net (code "42") (name "TDI") (class "Default")
      (node (ref "J_TO_MASTER") (pin "3") (pinfunction "3_3") (pintype "passive"))
      (node (ref "X1") (pin "2") (pinfunction "TDI_2") (pintype "bidirectional"))
      (node (ref "XTAG") (pin "5") (pinfunction "5_5") (pintype "passive"))
    )
    (net (code "43") (name "TDO") (class "Default")
      (node (ref "J_TO_SLAVE") (pin "3") (pinfunction "3_3") (pintype "passive"))
      (node (ref "TDO") (pin "1") (pinfunction "1_1") (pintype "passive"))
      (node (ref "X1") (pin "1") (pinfunction "TDO_1") (pintype "bidirectional"))
    )
    (net (code "44") (name "TDO_CHAIN") (class "Default")
      (node (ref "J_TO_MASTER") (pin "1") (pinfunction "1_1") (pintype "passive"))
      (node (ref "J_TO_SLAVE") (pin "1") (pinfunction "1_1") (pintype "passive"))
      (node (ref "TDO") (pin "3") (pinfunction "3_3") (pintype "passive"))
    )
    (net (code "45") (name "TDO_XTAG") (class "Default")
      (node (ref "TDO") (pin "2") (pinfunction "2_2") (pintype "passive"))
      (node (ref "TDO") (pin "4") (pinfunction "4_4") (pintype "passive"))
      (node (ref "XTAG") (pin "13") (pinfunction "13_13") (pintype "passive"))
    )
    (net (code "46") (name "TMS") (class "Default")
      (node (ref "J_TO_MASTER") (pin "4") (pinfunction "4_4") (pintype "passive"))
      (node (ref "J_TO_SLAVE") (pin "4") (pinfunction "4_4") (pintype "passive"))
      (node (ref "R24") (pin "1") (pinfunction "1_1") (pintype "passive"))
      (node (ref "X1") (pin "127") (pinfunction "TMS_127") (pintype "bidirectional"))
    )
    (net (code "47") (name "TX0") (class "Default")
      (node (ref "J0") (pin "119") (pinfunction "UART0_TX_119") (pintype "passive"))
      (node (ref "R16") (pin "1") (pinfunction "1_1") (pintype "passive"))
    )
    (net (code "48") (name "TX1") (class "Default")
      (node (ref "J0") (pin "117") (pinfunction "UART1_TX_117") (pintype "passive"))
      (node (ref "R18") (pin "1") (pinfunction "1_1") (pintype "passive"))
    )
    (net (code "49") (name "USB_N") (class "Default")
      (node (ref "J0") (pin "111") (pinfunction "USB_DN_111") (pintype "passive"))
      (node (ref "X1") (pin "47") (pinfunction "USB_DN_47") (pintype "bidirectional"))
    )
    (net (code "50") (name "USB_P") (class "Default")
      (node (ref "J0") (pin "112") (pinfunction "USB_DP_112") (pintype "passive"))
      (node (ref "X1") (pin "46") (pinfunction "USB_DP_46") (pintype "bidirectional"))
    )
    (net (code "51") (name "X0D00") (class "Default")
      (node (ref "J_TO_MASTER") (pin "61") (pinfunction "61_61") (pintype "passive"))
      (node (ref "X1") (pin "30") (pinfunction "X0D00_30") (pintype "bidirectional"))
    )
    (net (code "52") (name "X0D01") (class "Default")
      (node (ref "J_TO_MASTER") (pin "58") (pinfunction "58_58") (pintype "passive"))
      (node (ref "R9") (pin "2") (pinfunction "2_2") (pintype "passive"))
      (node (ref "X1") (pin "27") (pinfunction "X0D01_27") (pintype "bidirectional"))
    )
    (net (code "53") (name "X0D02") (class "Default")
      (node (ref "J_TO_MASTER") (pin "70") (pinfunction "70_70") (pintype "passive"))
      (node (ref "X1") (pin "37") (pinfunction "X0D02_37") (pintype "bidirectional"))
    )
    (net (code "54") (name "X0D03") (class "Default")
      (node (ref "J_TO_MASTER") (pin "72") (pinfunction "72_72") (pintype "passive"))
      (node (ref "X1") (pin "38") (pinfunction "X0D03_38") (pintype "bidirectional"))
    )
    (net (code "55") (name "X0D04") (class "Default")
      (node (ref "J_TO_MASTER") (pin "63") (pinfunction "63_63") (pintype "passive"))
      (node (ref "X1") (pin "31") (pinfunction "X0D04_31") (pintype "bidirectional"))
    )
    (net (code "56") (name "X0D05") (class "Default")
      (node (ref "J_TO_MASTER") (pin "66") (pinfunction "66_66") (pintype "passive"))
      (node (ref "X1") (pin "33") (pinfunction "X0D05_33") (pintype "bidirectional"))
    )
    (net (code "57") (name "X0D06") (class "Default")
      (node (ref "J_TO_MASTER") (pin "67") (pinfunction "67_67") (pintype "passive"))
      (node (ref "X1") (pin "34") (pinfunction "X0D06_34") (pintype "bidirectional"))
    )
    (net (code "58") (name "X0D07") (class "Default")
      (node (ref "J_TO_MASTER") (pin "69") (pinfunction "69_69") (pintype "passive"))
      (node (ref "X1") (pin "35") (pinfunction "X0D07_35") (pintype "bidirectional"))
    )
    (net (code "59") (name "X0D08") (class "Default")
      (node (ref "J_TO_MASTER") (pin "73") (pinfunction "73_73") (pintype "passive"))
      (node (ref "R21") (pin "2") (pinfunction "2_2") (pintype "passive"))
      (node (ref "X1") (pin "39") (pinfunction "X0D08_39") (pintype "bidirectional"))
    )
    (net (code "60") (name "X0D09") (class "Default")
      (node (ref "J_TO_MASTER") (pin "75") (pinfunction "75_75") (pintype "passive"))
      (node (ref "R22") (pin "2") (pinfunction "2_2") (pintype "passive"))
      (node (ref "X1") (pin "40") (pinfunction "X0D09_40") (pintype "bidirectional"))
    )
    (net (code "61") (name "X0D10") (class "Default")
      (node (ref "J_TO_MASTER") (pin "60") (pinfunction "60_60") (pintype "passive"))
      (node (ref "X1") (pin "28") (pinfunction "X0D10_28") (pintype "bidirectional"))
    )
    (net (code "62") (name "X0D11") (class "Default")
      (node (ref "J_TO_MASTER") (pin "64") (pinfunction "64_64") (pintype "passive"))
      (node (ref "R28") (pin "2") (pinfunction "2_2") (pintype "passive"))
      (node (ref "X0D11") (pin "TP") (pinfunction "TP_TP") (pintype "input"))
      (node (ref "X1") (pin "32") (pinfunction "X0D11_32") (pintype "bidirectional"))
    )
    (net (code "63") (name "X0D12") (class "Default")
      (node (ref "J_TO_SLAVE") (pin "63") (pinfunction "63_63") (pintype "passive"))
      (node (ref "X1") (pin "62") (pinfunction "X0D12_62") (pintype "bidirectional"))
    )
    (net (code "64") (name "X0D13") (class "Default")
      (node (ref "J_TO_SLAVE") (pin "61") (pinfunction "61_61") (pintype "passive"))
      (node (ref "X1") (pin "63") (pinfunction "X0D13_63") (pintype "bidirectional"))
    )
    (net (code "65") (name "X0D14") (class "Default")
      (node (ref "J_TO_SLAVE") (pin "69") (pinfunction "69_69") (pintype "passive"))
      (node (ref "R15") (pin "2") (pinfunction "2_2") (pintype "passive"))
      (node (ref "X1") (pin "57") (pinfunction "X0D14_57") (pintype "bidirectional"))
    )
    (net (code "66") (name "X0D15") (class "Default")
      (node (ref "J_TO_SLAVE") (pin "67") (pinfunction "67_67") (pintype "passive"))
      (node (ref "R17") (pin "2") (pinfunction "2_2") (pintype "passive"))
      (node (ref "X1") (pin "58") (pinfunction "X0D15_58") (pintype "bidirectional"))
    )
    (net (code "67") (name "X0D16") (class "Default")
      (node (ref "J_TO_SLAVE") (pin "57") (pinfunction "57_57") (pintype "passive"))
      (node (ref "X1") (pin "68") (pinfunction "X0D16_68") (pintype "bidirectional"))
    )
    (net (code "68") (name "X0D17") (class "Default")
      (node (ref "J_TO_SLAVE") (pin "55") (pinfunction "55_55") (pintype "passive"))
      (node (ref "X1") (pin "69") (pinfunction "X0D17_69") (pintype "bidirectional"))
    )
    (net (code "69") (name "X0D18") (class "Default")
      (node (ref "J_TO_SLAVE") (pin "54") (pinfunction "54_54") (pintype "passive"))
      (node (ref "X1") (pin "70") (pinfunction "X0D18_70") (pintype "bidirectional"))
    )
    (net (code "70") (name "X0D19") (class "Default")
      (node (ref "J_TO_SLAVE") (pin "52") (pinfunction "52_52") (pintype "passive"))
      (node (ref "X1") (pin "71") (pinfunction "X0D19_71") (pintype "bidirectional"))
    )
    (net (code "71") (name "X0D20") (class "Default")
      (node (ref "J_TO_SLAVE") (pin "66") (pinfunction "66_66") (pintype "passive"))
      (node (ref "R29") (pin "2") (pinfunction "2_2") (pintype "passive"))
      (node (ref "X1") (pin "59") (pinfunction "X0D20_59") (pintype "bidirectional"))
    )
    (net (code "72") (name "X0D21") (class "Default")
      (node (ref "J_TO_SLAVE") (pin "64") (pinfunction "64_64") (pintype "passive"))
      (node (ref "X1") (pin "61") (pinfunction "X0D21_61") (pintype "bidirectional"))
    )
    (net (code "73") (name "X0D22") (class "Default")
      (node (ref "J_TO_SLAVE") (pin "60") (pinfunction "60_60") (pintype "passive"))
      (node (ref "R20") (pin "2") (pinfunction "2_2") (pintype "passive"))
      (node (ref "X1") (pin "64") (pinfunction "X0D22_64") (pintype "bidirectional"))
    )
    (net (code "74") (name "X0D23") (class "Default")
      (node (ref "J_TO_SLAVE") (pin "58") (pinfunction "58_58") (pintype "passive"))
      (node (ref "R19") (pin "2") (pinfunction "2_2") (pintype "passive"))
      (node (ref "X1") (pin "66") (pinfunction "X0D23_66") (pintype "bidirectional"))
    )
    (net (code "75") (name "X0D24") (class "Default")
      (node (ref "J_TO_SLAVE") (pin "36") (pinfunction "36_36") (pintype "passive"))
      (node (ref "X1") (pin "88") (pinfunction "X0D24_88") (pintype "bidirectional"))
    )
    (net (code "76") (name "X0D25") (class "Default")
      (node (ref "J_TO_SLAVE") (pin "34") (pinfunction "34_34") (pintype "passive"))
      (node (ref "X1") (pin "89") (pinfunction "X0D25_89") (pintype "bidirectional"))
    )
    (net (code "77") (name "X0D26") (class "Default")
      (node (ref "J_TO_SLAVE") (pin "30") (pinfunction "30_30") (pintype "passive"))
      (node (ref "R16") (pin "2") (pinfunction "2_2") (pintype "passive"))
      (node (ref "X1") (pin "93") (pinfunction "X0D26_93") (pintype "bidirectional"))
    )
    (net (code "78") (name "X0D27") (class "Default")
      (node (ref "J_TO_SLAVE") (pin "28") (pinfunction "28_28") (pintype "passive"))
      (node (ref "R18") (pin "2") (pinfunction "2_2") (pintype "passive"))
      (node (ref "X1") (pin "94") (pinfunction "X0D27_94") (pintype "bidirectional"))
    )
    (net (code "79") (name "X0D28") (class "Default")
      (node (ref "J_TO_SLAVE") (pin "25") (pinfunction "25_25") (pintype "passive"))
      (node (ref "R23") (pin "2") (pinfunction "2_2") (pintype "passive"))
      (node (ref "X1") (pin "96") (pinfunction "X0D28_96") (pintype "bidirectional"))
    )
    (net (code "80") (name "X0D29") (class "Default")
      (node (ref "J_TO_SLAVE") (pin "22") (pinfunction "22_22") (pintype "passive"))
      (node (ref "X1") (pin "98") (pinfunction "X0D29_98") (pintype "bidirectional"))
    )
    (net (code "81") (name "X0D30") (class "Default")
      (node (ref "J_TO_SLAVE") (pin "21") (pinfunction "21_21") (pintype "passive"))
      (node (ref "X1") (pin "99") (pinfunction "X0D30_99") (pintype "bidirectional"))
    )
    (net (code "82") (name "X0D31") (class "Default")
      (node (ref "J_TO_SLAVE") (pin "19") (pinfunction "19_19") (pintype "passive"))
      (node (ref "X1") (pin "100") (pinfunction "X0D31_100") (pintype "bidirectional"))
    )
    (net (code "83") (name "X0D32") (class "Default")
      (node (ref "J_TO_SLAVE") (pin "27") (pinfunction "27_27") (pintype "passive"))
      (node (ref "X1") (pin "95") (pinfunction "X0D32_95") (pintype "bidirectional"))
    )
    (net (code "84") (name "X0D33") (class "Default")
      (node (ref "J_TO_SLAVE") (pin "24") (pinfunction "24_24") (pintype "passive"))
      (node (ref "X1") (pin "97") (pinfunction "X0D33_97") (pintype "bidirectional"))
    )
    (net (code "85") (name "X0D34") (class "Default")
      (node (ref "J_TO_SLAVE") (pin "33") (pinfunction "33_33") (pintype "passive"))
      (node (ref "X1") (pin "90") (pinfunction "X0D34_90") (pintype "bidirectional"))
    )
    (net (code "86") (name "X0D35") (class "Default")
      (node (ref "J_TO_SLAVE") (pin "31") (pinfunction "31_31") (pintype "passive"))
      (node (ref "X1") (pin "91") (pinfunction "X0D35_91") (pintype "bidirectional"))
    )
    (net (code "87") (name "X0D36") (class "Default")
      (node (ref "J_TO_MASTER") (pin "36") (pinfunction "36_36") (pintype "passive"))
      (node (ref "X1") (pin "3") (pinfunction "X0D36_3") (pintype "bidirectional"))
    )
    (net (code "88") (name "X0D37") (class "Default")
      (node (ref "J_TO_MASTER") (pin "40") (pinfunction "40_40") (pintype "passive"))
      (node (ref "X1") (pin "4") (pinfunction "X0D37_4") (pintype "bidirectional"))
    )
    (net (code "89") (name "X0D38") (class "Default")
      (node (ref "R30") (pin "2") (pinfunction "2_2") (pintype "passive"))
      (node (ref "X1") (pin "5") (pinfunction "X0D38_5") (pintype "bidirectional"))
    )
    (net (code "90") (name "X0D38_N") (class "Default")
      (node (ref "J_TO_MASTER") (pin "39") (pinfunction "39_39") (pintype "passive"))
      (node (ref "U4") (pin "4") (pinfunction "RIN-_4") (pintype "input"))
    )
    (net (code "91") (name "X0D38_P") (class "Default")
      (node (ref "J_TO_MASTER") (pin "37") (pinfunction "37_37") (pintype "passive"))
      (node (ref "U4") (pin "3") (pinfunction "RIN+_3") (pintype "input"))
    )
    (net (code "92") (name "X0D39") (class "Default")
      (node (ref "R31") (pin "1") (pinfunction "1_1") (pintype "passive"))
      (node (ref "X1") (pin "7") (pinfunction "X0D39_7") (pintype "bidirectional"))
    )
    (net (code "93") (name "X0D39_N") (class "Default")
      (node (ref "J_TO_MASTER") (pin "43") (pinfunction "43_43") (pintype "passive"))
      (node (ref "R33") (pin "2") (pinfunction "2_2") (pintype "passive"))
    )
    (net (code "94") (name "X0D39_P") (class "Default")
      (node (ref "J_TO_MASTER") (pin "45") (pinfunction "45_45") (pintype "passive"))
      (node (ref "R32") (pin "2") (pinfunction "2_2") (pintype "passive"))
    )
    (net (code "95") (name "X1D00") (class "Default")
      (node (ref "J_TO_SLAVE") (pin "39") (pinfunction "39_39") (pintype "passive"))
      (node (ref "R27") (pin "2") (pinfunction "2_2") (pintype "passive"))
      (node (ref "X1") (pin "85") (pinfunction "X1D00_85") (pintype "bidirectional"))
      (node (ref "X1D00") (pin "TP") (pinfunction "TP_TP") (pintype "input"))
    )
    (net (code "96") (name "X1D01") (class "Default")
      (node (ref "J_TO_SLAVE") (pin "37") (pinfunction "37_37") (pintype "passive"))
      (node (ref "X1") (pin "86") (pinfunction "X1D01_86") (pintype "bidirectional"))
    )
    (net (code "97") (name "X1D02") (class "Default")
      (node (ref "J_TO_SLAVE") (pin "51") (pinfunction "51_51") (pintype "passive"))
      (node (ref "X1") (pin "72") (pinfunction "X1D02_72") (pintype "bidirectional"))
    )
    (net (code "98") (name "X1D03") (class "Default")
      (node (ref "J_TO_SLAVE") (pin "49") (pinfunction "49_49") (pintype "passive"))
      (node (ref "R10") (pin "1") (pinfunction "1_1") (pintype "passive"))
    )
    (net (code "99") (name "X1D04") (class "Default")
      (node (ref "J_TO_SLAVE") (pin "48") (pinfunction "48_48") (pintype "passive"))
      (node (ref "R11") (pin "1") (pinfunction "1_1") (pintype "passive"))
    )
    (net (code "100") (name "X1D05") (class "Default")
      (node (ref "J_TO_SLAVE") (pin "46") (pinfunction "46_46") (pintype "passive"))
      (node (ref "R12") (pin "1") (pinfunction "1_1") (pintype "passive"))
    )
    (net (code "101") (name "X1D06") (class "Default")
      (node (ref "J_TO_SLAVE") (pin "45") (pinfunction "45_45") (pintype "passive"))
      (node (ref "R13") (pin "1") (pinfunction "1_1") (pintype "passive"))
    )
    (net (code "102") (name "X1D07") (class "Default")
      (node (ref "J_TO_SLAVE") (pin "43") (pinfunction "43_43") (pintype "passive"))
      (node (ref "R14") (pin "1") (pinfunction "1_1") (pintype "passive"))
    )
    (net (code "103") (name "X1D08") (class "Default")
      (node (ref "J_TO_SLAVE") (pin "42") (pinfunction "42_42") (pintype "passive"))
      (node (ref "X1") (pin "82") (pinfunction "X1D08_82") (pintype "bidirectional"))
    )
    (net (code "104") (name "X1D09") (class "Default")
      (node (ref "J_TO_SLAVE") (pin "40") (pinfunction "40_40") (pintype "passive"))
      (node (ref "X1") (pin "84") (pinfunction "X1D09_84") (pintype "bidirectional"))
    )
    (net (code "105") (name "X1D10") (class "Default")
      (node (ref "J_TO_MASTER") (pin "33") (pinfunction "33_33") (pintype "passive"))
      (node (ref "X1") (pin "121") (pinfunction "X1D10_121") (pintype "bidirectional"))
    )
    (net (code "106") (name "X1D11") (class "Default")
      (node (ref "J_TO_MASTER") (pin "34") (pinfunction "34_34") (pintype "passive"))
      (node (ref "X1") (pin "122") (pinfunction "X1D11_122") (pintype "bidirectional"))
    )
    (net (code "107") (name "X1D14") (class "Default")
      (node (ref "J_TO_SLAVE") (pin "75") (pinfunction "75_75") (pintype "passive"))
      (node (ref "X1") (pin "51") (pinfunction "X1D14_51") (pintype "bidirectional"))
    )
    (net (code "108") (name "X1D15") (class "Default")
      (node (ref "J_TO_SLAVE") (pin "73") (pinfunction "73_73") (pintype "passive"))
      (node (ref "X1") (pin "53") (pinfunction "X1D15_53") (pintype "bidirectional"))
    )
    (net (code "109") (name "X1D16") (class "Default")
      (node (ref "J_TO_MASTER") (pin "52") (pinfunction "52_52") (pintype "passive"))
      (node (ref "X1") (pin "22") (pinfunction "X1D16_22") (pintype "bidirectional"))
    )
    (net (code "110") (name "X1D17") (class "Default")
      (node (ref "J_TO_MASTER") (pin "54") (pinfunction "54_54") (pintype "passive"))
      (node (ref "X1") (pin "23") (pinfunction "X1D17_23") (pintype "bidirectional"))
    )
    (net (code "111") (name "X1D18") (class "Default")
      (node (ref "J_TO_MASTER") (pin "55") (pinfunction "55_55") (pintype "passive"))
      (node (ref "X1") (pin "25") (pinfunction "X1D18_25") (pintype "bidirectional"))
    )
    (net (code "112") (name "X1D19") (class "Default")
      (node (ref "J_TO_MASTER") (pin "57") (pinfunction "57_57") (pintype "passive"))
      (node (ref "X1") (pin "26") (pinfunction "X1D19_26") (pintype "bidirectional"))
    )
    (net (code "113") (name "X1D20") (class "Default")
      (node (ref "J_TO_SLAVE") (pin "72") (pinfunction "72_72") (pintype "passive"))
      (node (ref "X1") (pin "54") (pinfunction "X1D20_54") (pintype "bidirectional"))
    )
    (net (code "114") (name "X1D21") (class "Default")
      (node (ref "J_TO_SLAVE") (pin "70") (pinfunction "70_70") (pintype "passive"))
      (node (ref "X1") (pin "55") (pinfunction "X1D21_55") (pintype "bidirectional"))
    )
    (net (code "115") (name "X1D26") (class "Default")
      (node (ref "J_TO_MASTER") (pin "21") (pinfunction "21_21") (pintype "passive"))
      (node (ref "X1") (pin "112") (pinfunction "X1D26_112") (pintype "bidirectional"))
    )
    (net (code "116") (name "X1D27") (class "Default")
      (node (ref "J_TO_MASTER") (pin "22") (pinfunction "22_22") (pintype "passive"))
      (node (ref "X1") (pin "113") (pinfunction "X1D27_113") (pintype "bidirectional"))
    )
    (net (code "117") (name "X1D28") (class "Default")
      (node (ref "J_TO_MASTER") (pin "24") (pinfunction "24_24") (pintype "passive"))
      (node (ref "X1") (pin "114") (pinfunction "X1D28_114") (pintype "bidirectional"))
    )
    (net (code "118") (name "X1D29") (class "Default")
      (node (ref "J_TO_MASTER") (pin "25") (pinfunction "25_25") (pintype "passive"))
      (node (ref "X1") (pin "115") (pinfunction "X1D29_115") (pintype "bidirectional"))
    )
    (net (code "119") (name "X1D30") (class "Default")
      (node (ref "J_TO_MASTER") (pin "27") (pinfunction "27_27") (pintype "passive"))
      (node (ref "X1") (pin "116") (pinfunction "X1D30_116") (pintype "bidirectional"))
    )
    (net (code "120") (name "X1D31") (class "Default")
      (node (ref "J_TO_MASTER") (pin "28") (pinfunction "28_28") (pintype "passive"))
      (node (ref "X1") (pin "117") (pinfunction "X1D31_117") (pintype "bidirectional"))
    )
    (net (code "121") (name "X1D32") (class "Default")
      (node (ref "J_TO_MASTER") (pin "30") (pinfunction "30_30") (pintype "passive"))
      (node (ref "X1") (pin "118") (pinfunction "X1D32_118") (pintype "bidirectional"))
    )
    (net (code "122") (name "X1D33") (class "Default")
      (node (ref "J_TO_MASTER") (pin "31") (pinfunction "31_31") (pintype "passive"))
      (node (ref "X1") (pin "119") (pinfunction "X1D33_119") (pintype "bidirectional"))
    )
    (net (code "123") (name "X1D35") (class "Default")
      (node (ref "J_TO_MASTER") (pin "42") (pinfunction "42_42") (pintype "passive"))
      (node (ref "X1") (pin "13") (pinfunction "X1D35_13") (pintype "bidirectional"))
    )
    (net (code "124") (name "X1D36") (class "Default")
      (node (ref "J_TO_MASTER") (pin "46") (pinfunction "46_46") (pintype "passive"))
      (node (ref "X1") (pin "15") (pinfunction "X1D36_15") (pintype "bidirectional"))
    )
    (net (code "125") (name "X1D37") (class "Default")
      (node (ref "J_TO_MASTER") (pin "48") (pinfunction "48_48") (pintype "passive"))
      (node (ref "X1") (pin "18") (pinfunction "X1D37_18") (pintype "bidirectional"))
    )
    (net (code "126") (name "X1D38") (class "Default")
      (node (ref "J_TO_MASTER") (pin "49") (pinfunction "49_49") (pintype "passive"))
      (node (ref "X1") (pin "20") (pinfunction "X1D38_20") (pintype "bidirectional"))
    )
    (net (code "127") (name "X1D39") (class "Default")
      (node (ref "J_TO_MASTER") (pin "51") (pinfunction "51_51") (pintype "passive"))
      (node (ref "X1") (pin "21") (pinfunction "X1D39_21") (pintype "bidirectional"))
    )
    (net (code "128") (name "X1D40") (class "Default")
      (node (ref "J_TO_MASTER") (pin "9") (pinfunction "9_9") (pintype "passive"))
      (node (ref "X1") (pin "106") (pinfunction "X1D40_106") (pintype "bidirectional"))
    )
    (net (code "129") (name "X1D41") (class "Default")
      (node (ref "J_TO_MASTER") (pin "16") (pinfunction "16_16") (pintype "passive"))
      (node (ref "X1") (pin "107") (pinfunction "X1D41_107") (pintype "bidirectional"))
    )
    (net (code "130") (name "X1D42") (class "Default")
      (node (ref "J_TO_MASTER") (pin "18") (pinfunction "18_18") (pintype "passive"))
      (node (ref "X1") (pin "108") (pinfunction "X1D42_108") (pintype "bidirectional"))
    )
    (net (code "131") (name "X1D43") (class "Default")
      (node (ref "J_TO_MASTER") (pin "19") (pinfunction "19_19") (pintype "passive"))
      (node (ref "X1") (pin "109") (pinfunction "X1D43_109") (pintype "bidirectional"))
    )
    (net (code "132") (name "XL0_IN_0") (class "Default")
      (node (ref "X1") (pin "9") (pinfunction "X0D41_9") (pintype "bidirectional"))
      (node (ref "XTAG") (pin "14") (pinfunction "14_14") (pintype "passive"))
    )
    (net (code "133") (name "XL0_IN_1") (class "Default")
      (node (ref "X1") (pin "8") (pinfunction "X0D40_8") (pintype "bidirectional"))
      (node (ref "XTAG") (pin "18") (pinfunction "18_18") (pintype "passive"))
    )
    (net (code "134") (name "XL0_OUT_0") (class "Default")
      (node (ref "R5") (pin "1") (pinfunction "1_1") (pintype "passive"))
      (node (ref "XTAG") (pin "10") (pinfunction "10_10") (pintype "passive"))
    )
    (net (code "135") (name "XL0_OUT_1") (class "Default")
      (node (ref "R4") (pin "1") (pinfunction "1_1") (pintype "passive"))
      (node (ref "XTAG") (pin "6") (pinfunction "6_6") (pintype "passive"))
    )
    (net (code "136") (name "XSYS_RST_N") (class "Default")
      (node (ref "J_TO_MASTER") (pin "7") (pinfunction "7_7") (pintype "passive"))
      (node (ref "J_TO_SLAVE") (pin "7") (pinfunction "7_7") (pintype "passive"))
      (node (ref "R1") (pin "1") (pinfunction "1_1") (pintype "passive"))
      (node (ref "R26") (pin "1") (pinfunction "1_1") (pintype "passive"))
      (node (ref "U1") (pin "3") (pinfunction "A2_3") (pintype "input"))
    )
    (net (code "137") (name "unconnected-(J0A-IO3-Pad108)") (class "Default")
      (node (ref "J0") (pin "108") (pinfunction "IO3_108") (pintype "passive"))
    )
    (net (code "138") (name "unconnected-(J0A-IO4-Pad105)") (class "Default")
      (node (ref "J0") (pin "105") (pinfunction "IO4_105") (pintype "passive"))
    )
    (net (code "139") (name "unconnected-(J0A-IO5-Pad106)") (class "Default")
      (node (ref "J0") (pin "106") (pinfunction "IO5_106") (pintype "passive"))
    )
    (net (code "140") (name "unconnected-(J0B-GND0-Pad2)") (class "Default")
      (node (ref "J0") (pin "2") (pinfunction "GND0_2") (pintype "passive"))
    )
    (net (code "141") (name "unconnected-(J0B-GND1-Pad4)") (class "Default")
      (node (ref "J0") (pin "4") (pinfunction "GND1_4") (pintype "passive"))
    )
    (net (code "142") (name "unconnected-(J0B-GND2-Pad6)") (class "Default")
      (node (ref "J0") (pin "6") (pinfunction "GND2_6") (pintype "passive"))
    )
    (net (code "143") (name "unconnected-(J0B-GND3-Pad8)") (class "Default")
      (node (ref "J0") (pin "8") (pinfunction "GND3_8") (pintype "passive"))
    )
    (net (code "144") (name "unconnected-(J0B-GND4-Pad10)") (class "Default")
      (node (ref "J0") (pin "10") (pinfunction "GND4_10") (pintype "passive"))
    )
    (net (code "145") (name "unconnected-(J0B-GND5-Pad12)") (class "Default")
      (node (ref "J0") (pin "12") (pinfunction "GND5_12") (pintype "passive"))
    )
    (net (code "146") (name "unconnected-(J0B-VCC0-Pad1)") (class "Default")
      (node (ref "J0") (pin "1") (pinfunction "VCC0_1") (pintype "passive"))
    )
    (net (code "147") (name "unconnected-(J0B-VCC1-Pad3)") (class "Default")
      (node (ref "J0") (pin "3") (pinfunction "VCC1_3") (pintype "passive"))
    )
    (net (code "148") (name "unconnected-(J0B-VCC2-Pad5)") (class "Default")
      (node (ref "J0") (pin "5") (pinfunction "VCC2_5") (pintype "passive"))
    )
    (net (code "149") (name "unconnected-(J0B-VCC3-Pad7)") (class "Default")
      (node (ref "J0") (pin "7") (pinfunction "VCC3_7") (pintype "passive"))
    )
    (net (code "150") (name "unconnected-(J0B-VCC4-Pad9)") (class "Default")
      (node (ref "J0") (pin "9") (pinfunction "VCC4_9") (pintype "passive"))
    )
    (net (code "151") (name "unconnected-(J0B-VCC5-Pad11)") (class "Default")
      (node (ref "J0") (pin "11") (pinfunction "VCC5_11") (pintype "passive"))
    )
    (net (code "152") (name "unconnected-(J_TO_SLAVE-Pad9)") (class "Default")
      (node (ref "J_TO_SLAVE") (pin "9") (pinfunction "9_9") (pintype "passive"))
    )
    (net (code "153") (name "unconnected-(J_TO_SLAVE-Pad16)") (class "Default")
      (node (ref "J_TO_SLAVE") (pin "16") (pinfunction "16_16") (pintype "passive"))
    )
    (net (code "154") (name "unconnected-(J_TO_SLAVE-Pad18)") (class "Default")
      (node (ref "J_TO_SLAVE") (pin "18") (pinfunction "18_18") (pintype "passive"))
    )
    (net (code "155") (name "unconnected-(XTAG-Pad1)") (class "Default")
      (node (ref "XTAG") (pin "1") (pinfunction "1_1") (pintype "passive"))
    )
    (net (code "156") (name "unconnected-(XTAG-Pad2)") (class "Default")
      (node (ref "XTAG") (pin "2") (pinfunction "2_2") (pintype "passive"))
    )
    (net (code "157") (name "unconnected-(XTAG-Pad3)") (class "Default")
      (node (ref "XTAG") (pin "3") (pinfunction "3_3") (pintype "passive"))
    )
    (net (code "158") (name "unconnected-(XTAG-Pad11)") (class "Default")
      (node (ref "XTAG") (pin "11") (pinfunction "11_11") (pintype "passive"))
    )
    (net (code "159") (name "unconnected-(XTAG-Pad17)") (class "Default")
      (node (ref "XTAG") (pin "17") (pinfunction "17_17") (pintype "passive"))
    )
    (net (code "160") (name "unconnected-(XTAG-Pad19)") (class "Default")
      (node (ref "XTAG") (pin "19") (pinfunction "19_19") (pintype "passive"))
    )
  )
)
